# Ecran.net
KiCad netlist of a schematic drawn in Altium Designer
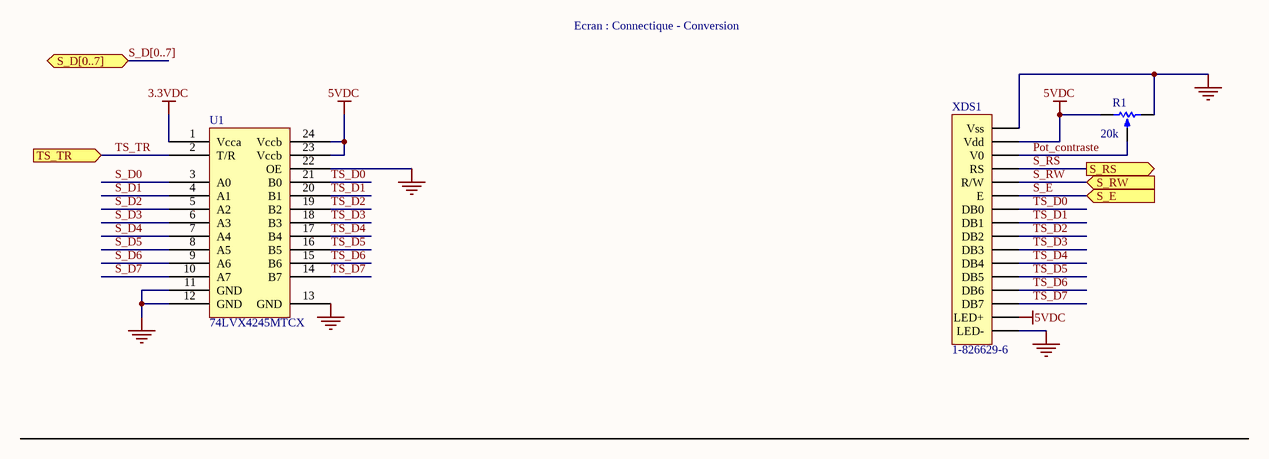
[diagram p0: Ecran.SchDoc]

(export (version "E")
  (design (tool "Eeschema 10.0.6"))
  (components
    (comp (ref "R1")
      (value "20k")
      (footprint "VR5")
      (description "Potentiometer")
      (libsource (lib "Miscellaneous Devices") (part "RPot"))
    )
    (comp (ref "U1")
      (value "74LVX4245MTCX")
      (description "Bus Transceiver")
      (libsource (lib "Schlib1") (part "74LVX4245MTCX"))
    )
    (comp (ref "XDS1")
      (value "1-826629-6")
      (footprint "HDR1X16")
      (description "Header, 16-Pin")
      (libsource (lib "Miscellaneous Connectors") (part "Header 16"))
    )
  )
  (nets
    (net (code "1") (name "/Pot_contraste") (class "Default")
      (node (ref "R1") (pin "3") (pinfunction "TAP_3") (pintype "passive"))
      (node (ref "XDS1") (pin "3") (pinfunction "V0_3") (pintype "passive"))
    )
    (net (code "2") (name "/S_D0") (class "Default")
      (node (ref "U1") (pin "3") (pinfunction "A0_3") (pintype "passive"))
    )
    (net (code "3") (name "/S_D1") (class "Default")
      (node (ref "U1") (pin "4") (pinfunction "A1_4") (pintype "passive"))
    )
    (net (code "4") (name "/S_D2") (class "Default")
      (node (ref "U1") (pin "5") (pinfunction "A2_5") (pintype "passive"))
    )
    (net (code "5") (name "/S_D3") (class "Default")
      (node (ref "U1") (pin "6") (pinfunction "A3_6") (pintype "passive"))
    )
    (net (code "6") (name "/S_D4") (class "Default")
      (node (ref "U1") (pin "7") (pinfunction "A4_7") (pintype "passive"))
    )
    (net (code "7") (name "/S_D5") (class "Default")
      (node (ref "U1") (pin "8") (pinfunction "A5_8") (pintype "passive"))
    )
    (net (code "8") (name "/S_D6") (class "Default")
      (node (ref "U1") (pin "9") (pinfunction "A6_9") (pintype "passive"))
    )
    (net (code "9") (name "/S_D7") (class "Default")
      (node (ref "U1") (pin "10") (pinfunction "A7_10") (pintype "passive"))
    )
    (net (code "11") (name "/S_E") (class "Default")
      (node (ref "XDS1") (pin "6") (pinfunction "E_6") (pintype "passive"))
    )
    (net (code "12") (name "/S_RS") (class "Default")
      (node (ref "XDS1") (pin "4") (pinfunction "RS_4") (pintype "passive"))
    )
    (net (code "13") (name "/S_RW") (class "Default")
      (node (ref "XDS1") (pin "5") (pinfunction "R/W_5") (pintype "passive"))
    )
    (net (code "14") (name "/TS_D0") (class "Default")
      (node (ref "U1") (pin "21") (pinfunction "B0_21") (pintype "passive"))
      (node (ref "XDS1") (pin "7") (pinfunction "DB0_7") (pintype "passive"))
    )
    (net (code "15") (name "/TS_D1") (class "Default")
      (node (ref "U1") (pin "20") (pinfunction "B1_20") (pintype "passive"))
      (node (ref "XDS1") (pin "8") (pinfunction "DB1_8") (pintype "passive"))
    )
    (net (code "16") (name "/TS_D2") (class "Default")
      (node (ref "U1") (pin "19") (pinfunction "B2_19") (pintype "passive"))
      (node (ref "XDS1") (pin "9") (pinfunction "DB2_9") (pintype "passive"))
    )
    (net (code "17") (name "/TS_D3") (class "Default")
      (node (ref "U1") (pin "18") (pinfunction "B3_18") (pintype "passive"))
      (node (ref "XDS1") (pin "10") (pinfunction "DB3_10") (pintype "passive"))
    )
    (net (code "18") (name "/TS_D4") (class "Default")
      (node (ref "U1") (pin "17") (pinfunction "B4_17") (pintype "passive"))
      (node (ref "XDS1") (pin "11") (pinfunction "DB4_11") (pintype "passive"))
    )
    (net (code "19") (name "/TS_D5") (class "Default")
      (node (ref "U1") (pin "16") (pinfunction "B5_16") (pintype "passive"))
      (node (ref "XDS1") (pin "12") (pinfunction "DB5_12") (pintype "passive"))
    )
    (net (code "20") (name "/TS_D6") (class "Default")
      (node (ref "U1") (pin "15") (pinfunction "B6_15") (pintype "passive"))
      (node (ref "XDS1") (pin "13") (pinfunction "DB6_13") (pintype "passive"))
    )
    (net (code "21") (name "/TS_D7") (class "Default")
      (node (ref "U1") (pin "14") (pinfunction "B7_14") (pintype "passive"))
      (node (ref "XDS1") (pin "14") (pinfunction "DB7_14") (pintype "passive"))
    )
    (net (code "22") (name "/TS_TR") (class "Default")
      (node (ref "U1") (pin "2") (pinfunction "T/R_2") (pintype "passive"))
    )
    (net (code "23") (name "3.3VDC") (class "Default")
      (node (ref "U1") (pin "1") (pinfunction "Vcca_1") (pintype "passive"))
    )
    (net (code "24") (name "5VDC") (class "Default")
      (node (ref "R1") (pin "1") (pinfunction "TOP_1") (pintype "passive"))
      (node (ref "U1") (pin "23") (pinfunction "Vccb_23") (pintype "passive"))
      (node (ref "U1") (pin "24") (pinfunction "Vccb_24") (pintype "passive"))
      (node (ref "XDS1") (pin "15") (pinfunction "LED+_15") (pintype "passive"))
      (node (ref "XDS1") (pin "2") (pinfunction "Vdd_2") (pintype "passive"))
    )
    (net (code "25") (name "GND") (class "Default")
      (node (ref "R1") (pin "2") (pinfunction "BOT_2") (pintype "passive"))
      (node (ref "U1") (pin "11") (pinfunction "GND_11") (pintype "passive"))
      (node (ref "U1") (pin "12") (pinfunction "GND_12") (pintype "passive"))
      (node (ref "U1") (pin "13") (pinfunction "GND_13") (pintype "passive"))
      (node (ref "U1") (pin "22") (pinfunction "OE_22") (pintype "passive"))
      (node (ref "XDS1") (pin "1") (pinfunction "Vss_1") (pintype "passive"))
      (node (ref "XDS1") (pin "16") (pinfunction "LED-_16") (pintype "passive"))
    )
  )
)
